# R450X.net
KiCad netlist of a schematic drawn in EAGLE
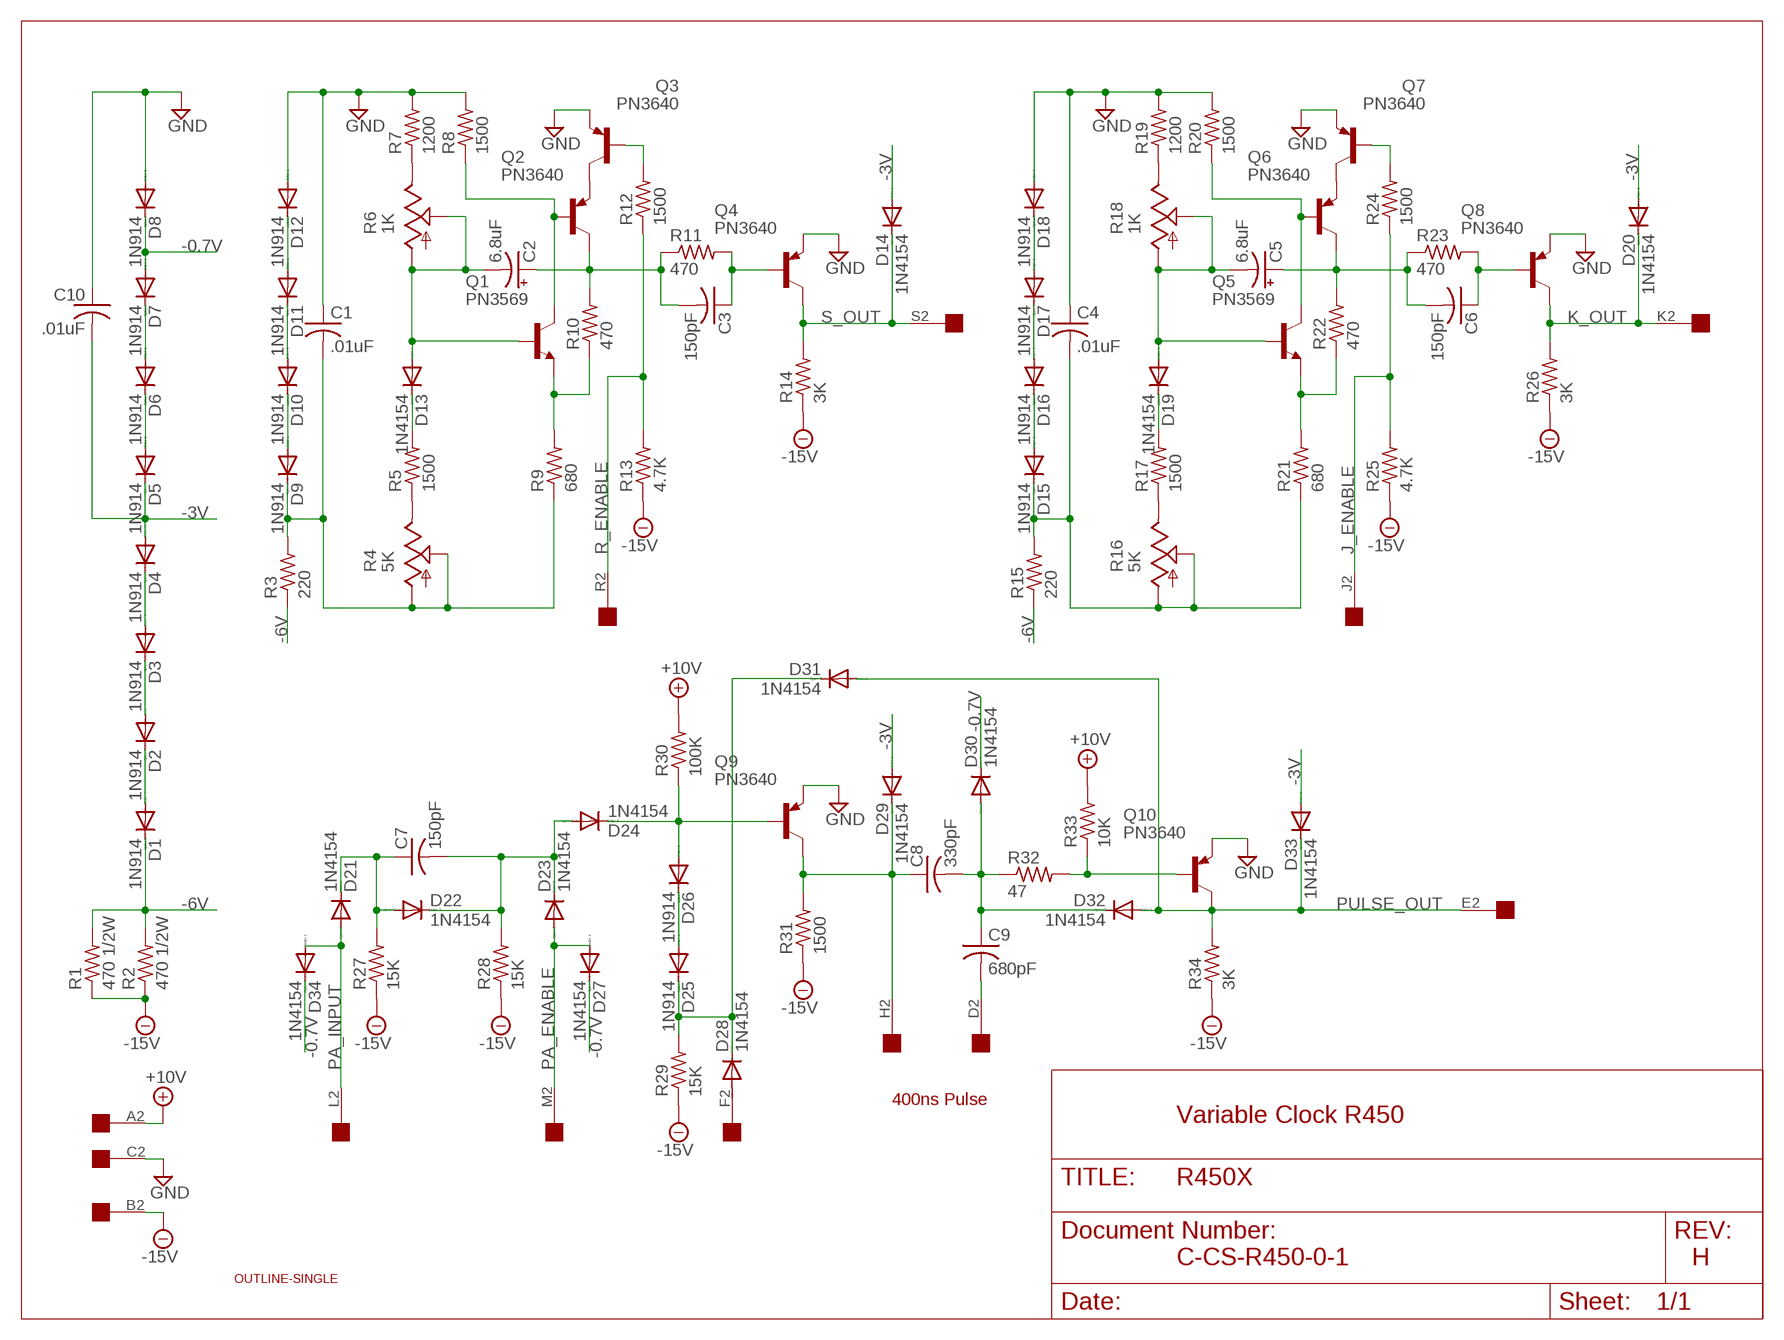
[diagram p0: schematic, sheet 1]

(export (version "E")
  (design (tool "Eeschema 10.0.6"))
  (components
    (comp (ref "C1")
      (value ".01uF")
      (footprint "eagle-import:C050-025X075")
      (libsource (lib "eagle-import") (part "C-US050-025X075"))
    )
    (comp (ref "C2")
      (value "6.8uF")
      (footprint "eagle-import:E12-4")
      (libsource (lib "eagle-import") (part "CPOL-USE12-4AXIAL"))
    )
    (comp (ref "C3")
      (value "150pF")
      (footprint "eagle-import:C075-032X103")
      (libsource (lib "eagle-import") (part "C-US075-032X103"))
    )
    (comp (ref "C4")
      (value ".01uF")
      (footprint "eagle-import:C050-025X075")
      (libsource (lib "eagle-import") (part "C-US050-025X075"))
    )
    (comp (ref "C5")
      (value "6.8uF")
      (footprint "eagle-import:E12-4")
      (libsource (lib "eagle-import") (part "CPOL-USE12-4AXIAL"))
    )
    (comp (ref "C6")
      (value "150pF")
      (footprint "eagle-import:C075-032X103")
      (libsource (lib "eagle-import") (part "C-US075-032X103"))
    )
    (comp (ref "C7")
      (value "150pF")
      (footprint "eagle-import:C075-032X103")
      (libsource (lib "eagle-import") (part "C-US075-032X103"))
    )
    (comp (ref "C8")
      (value "330pF")
      (footprint "eagle-import:C075-032X103")
      (libsource (lib "eagle-import") (part "C-US075-032X103"))
    )
    (comp (ref "C9")
      (value "680pF")
      (footprint "eagle-import:C075-032X103")
      (libsource (lib "eagle-import") (part "C-US075-032X103"))
    )
    (comp (ref "C10")
      (value ".01uF")
      (footprint "eagle-import:C050-025X075")
      (libsource (lib "eagle-import") (part "C-US050-025X075"))
    )
    (comp (ref "D1")
      (value "1N914")
      (footprint "eagle-import:DO35-10")
      (libsource (lib "eagle-import") (part "1N4148DO35-10"))
    )
    (comp (ref "D2")
      (value "1N914")
      (footprint "eagle-import:DO35-10")
      (libsource (lib "eagle-import") (part "1N4148DO35-10"))
    )
    (comp (ref "D3")
      (value "1N914")
      (footprint "eagle-import:DO35-10")
      (libsource (lib "eagle-import") (part "1N4148DO35-10"))
    )
    (comp (ref "D4")
      (value "1N914")
      (footprint "eagle-import:DO35-10")
      (libsource (lib "eagle-import") (part "1N4148DO35-10"))
    )
    (comp (ref "D5")
      (value "1N914")
      (footprint "eagle-import:DO35-10")
      (libsource (lib "eagle-import") (part "1N4148DO35-10"))
    )
    (comp (ref "D6")
      (value "1N914")
      (footprint "eagle-import:DO35-10")
      (libsource (lib "eagle-import") (part "1N4148DO35-10"))
    )
    (comp (ref "D7")
      (value "1N914")
      (footprint "eagle-import:DO35-10")
      (libsource (lib "eagle-import") (part "1N4148DO35-10"))
    )
    (comp (ref "D8")
      (value "1N914")
      (footprint "eagle-import:DO35-10")
      (libsource (lib "eagle-import") (part "1N4148DO35-10"))
    )
    (comp (ref "D9")
      (value "1N914")
      (footprint "eagle-import:DO35-10")
      (libsource (lib "eagle-import") (part "1N4148DO35-10"))
    )
    (comp (ref "D10")
      (value "1N914")
      (footprint "eagle-import:DO35-10")
      (libsource (lib "eagle-import") (part "1N4148DO35-10"))
    )
    (comp (ref "D11")
      (value "1N914")
      (footprint "eagle-import:DO35-10")
      (libsource (lib "eagle-import") (part "1N4148DO35-10"))
    )
    (comp (ref "D12")
      (value "1N914")
      (footprint "eagle-import:DO35-10")
      (libsource (lib "eagle-import") (part "1N4148DO35-10"))
    )
    (comp (ref "D13")
      (value "1N4154")
      (footprint "eagle-import:DO35-10")
      (libsource (lib "eagle-import") (part "1N4148DO35-10"))
    )
    (comp (ref "D14")
      (value "1N4154")
      (footprint "eagle-import:DO35-10")
      (libsource (lib "eagle-import") (part "1N4148DO35-10"))
    )
    (comp (ref "D15")
      (value "1N914")
      (footprint "eagle-import:DO35-10")
      (libsource (lib "eagle-import") (part "1N4148DO35-10"))
    )
    (comp (ref "D16")
      (value "1N914")
      (footprint "eagle-import:DO35-10")
      (libsource (lib "eagle-import") (part "1N4148DO35-10"))
    )
    (comp (ref "D17")
      (value "1N914")
      (footprint "eagle-import:DO35-10")
      (libsource (lib "eagle-import") (part "1N4148DO35-10"))
    )
    (comp (ref "D18")
      (value "1N914")
      (footprint "eagle-import:DO35-10")
      (libsource (lib "eagle-import") (part "1N4148DO35-10"))
    )
    (comp (ref "D19")
      (value "1N4154")
      (footprint "eagle-import:DO35-10")
      (libsource (lib "eagle-import") (part "1N4148DO35-10"))
    )
    (comp (ref "D20")
      (value "1N4154")
      (footprint "eagle-import:DO35-10")
      (libsource (lib "eagle-import") (part "1N4148DO35-10"))
    )
    (comp (ref "D21")
      (value "1N4154")
      (footprint "eagle-import:DO35-10")
      (libsource (lib "eagle-import") (part "1N4148DO35-10"))
    )
    (comp (ref "D22")
      (value "1N4154")
      (footprint "eagle-import:DO35-10")
      (libsource (lib "eagle-import") (part "1N4148DO35-10"))
    )
    (comp (ref "D23")
      (value "1N4154")
      (footprint "eagle-import:DO35-10")
      (libsource (lib "eagle-import") (part "1N4148DO35-10"))
    )
    (comp (ref "D24")
      (value "1N4154")
      (footprint "eagle-import:DO35-10")
      (libsource (lib "eagle-import") (part "1N4148DO35-10"))
    )
    (comp (ref "D25")
      (value "1N914")
      (footprint "eagle-import:DO35-10")
      (libsource (lib "eagle-import") (part "1N4148DO35-10"))
    )
    (comp (ref "D26")
      (value "1N914")
      (footprint "eagle-import:DO35-10")
      (libsource (lib "eagle-import") (part "1N4148DO35-10"))
    )
    (comp (ref "D27")
      (value "1N4154")
      (footprint "eagle-import:DO35-10")
      (libsource (lib "eagle-import") (part "1N4148DO35-10"))
    )
    (comp (ref "D28")
      (value "1N4154")
      (footprint "eagle-import:DO35-10")
      (libsource (lib "eagle-import") (part "1N4148DO35-10"))
    )
    (comp (ref "D29")
      (value "1N4154")
      (footprint "eagle-import:DO35-10")
      (libsource (lib "eagle-import") (part "1N4148DO35-10"))
    )
    (comp (ref "D30")
      (value "1N4154")
      (footprint "eagle-import:DO35-10")
      (libsource (lib "eagle-import") (part "1N4148DO35-10"))
    )
    (comp (ref "D31")
      (value "1N4154")
      (footprint "eagle-import:DO35-10")
      (libsource (lib "eagle-import") (part "1N4148DO35-10"))
    )
    (comp (ref "D32")
      (value "1N4154")
      (footprint "eagle-import:DO35-10")
      (libsource (lib "eagle-import") (part "1N4148DO35-10"))
    )
    (comp (ref "D33")
      (value "1N4154")
      (footprint "eagle-import:DO35-10")
      (libsource (lib "eagle-import") (part "1N4148DO35-10"))
    )
    (comp (ref "D34")
      (value "1N4154")
      (footprint "eagle-import:DO35-10")
      (libsource (lib "eagle-import") (part "1N4148DO35-10"))
    )
    (comp (ref "Q1")
      (value "PN3569")
      (footprint "eagle-import:TO5")
      (libsource (lib "eagle-import") (part "2N2102"))
    )
    (comp (ref "Q2")
      (value "PN3640")
      (footprint "eagle-import:TO39")
      (libsource (lib "eagle-import") (part "2N2904"))
    )
    (comp (ref "Q3")
      (value "PN3640")
      (footprint "eagle-import:TO39")
      (libsource (lib "eagle-import") (part "2N2904"))
    )
    (comp (ref "Q4")
      (value "PN3640")
      (footprint "eagle-import:TO39")
      (libsource (lib "eagle-import") (part "2N2904"))
    )
    (comp (ref "Q5")
      (value "PN3569")
      (footprint "eagle-import:TO5")
      (libsource (lib "eagle-import") (part "2N2102"))
    )
    (comp (ref "Q6")
      (value "PN3640")
      (footprint "eagle-import:TO39")
      (libsource (lib "eagle-import") (part "2N2904"))
    )
    (comp (ref "Q7")
      (value "PN3640")
      (footprint "eagle-import:TO39")
      (libsource (lib "eagle-import") (part "2N2904"))
    )
    (comp (ref "Q8")
      (value "PN3640")
      (footprint "eagle-import:TO39")
      (libsource (lib "eagle-import") (part "2N2904"))
    )
    (comp (ref "Q9")
      (value "PN3640")
      (footprint "eagle-import:TO39")
      (libsource (lib "eagle-import") (part "2N2904"))
    )
    (comp (ref "Q10")
      (value "PN3640")
      (footprint "eagle-import:TO39")
      (libsource (lib "eagle-import") (part "2N2904"))
    )
    (comp (ref "R1")
      (value "470 1/2W")
      (footprint "eagle-import:0411_15")
      (libsource (lib "eagle-import") (part "R-US_0411/15"))
    )
    (comp (ref "R2")
      (value "470 1/2W")
      (footprint "eagle-import:0411_15")
      (libsource (lib "eagle-import") (part "R-US_0411/15"))
    )
    (comp (ref "R3")
      (value "220")
      (footprint "eagle-import:0207_10")
      (libsource (lib "eagle-import") (part "R-US_0207/10"))
    )
    (comp (ref "R4")
      (value "5K")
      (footprint "eagle-import:CT6")
      (libsource (lib "eagle-import") (part "TRIM_US-CT6"))
    )
    (comp (ref "R5")
      (value "1500")
      (footprint "eagle-import:0207_10")
      (libsource (lib "eagle-import") (part "R-US_0207/10"))
    )
    (comp (ref "R6")
      (value "1K")
      (footprint "eagle-import:CT6")
      (libsource (lib "eagle-import") (part "TRIM_US-CT6"))
    )
    (comp (ref "R7")
      (value "1200")
      (footprint "eagle-import:0207_10")
      (libsource (lib "eagle-import") (part "R-US_0207/10"))
    )
    (comp (ref "R8")
      (value "1500")
      (footprint "eagle-import:0207_10")
      (libsource (lib "eagle-import") (part "R-US_0207/10"))
    )
    (comp (ref "R9")
      (value "680")
      (footprint "eagle-import:0207_10")
      (libsource (lib "eagle-import") (part "R-US_0207/10"))
    )
    (comp (ref "R10")
      (value "470")
      (footprint "eagle-import:0207_10")
      (libsource (lib "eagle-import") (part "R-US_0207/10"))
    )
    (comp (ref "R11")
      (value "470")
      (footprint "eagle-import:0207_10")
      (libsource (lib "eagle-import") (part "R-US_0207/10"))
    )
    (comp (ref "R12")
      (value "1500")
      (footprint "eagle-import:0207_10")
      (libsource (lib "eagle-import") (part "R-US_0207/10"))
    )
    (comp (ref "R13")
      (value "4.7K")
      (footprint "eagle-import:0207_10")
      (libsource (lib "eagle-import") (part "R-US_0207/10"))
    )
    (comp (ref "R14")
      (value "3K")
      (footprint "eagle-import:0207_10")
      (libsource (lib "eagle-import") (part "R-US_0207/10"))
    )
    (comp (ref "R15")
      (value "220")
      (footprint "eagle-import:0207_10")
      (libsource (lib "eagle-import") (part "R-US_0207/10"))
    )
    (comp (ref "R16")
      (value "5K")
      (footprint "eagle-import:CT6")
      (libsource (lib "eagle-import") (part "TRIM_US-CT6"))
    )
    (comp (ref "R17")
      (value "1500")
      (footprint "eagle-import:0207_10")
      (libsource (lib "eagle-import") (part "R-US_0207/10"))
    )
    (comp (ref "R18")
      (value "1K")
      (footprint "eagle-import:CT6")
      (libsource (lib "eagle-import") (part "TRIM_US-CT6"))
    )
    (comp (ref "R19")
      (value "1200")
      (footprint "eagle-import:0207_10")
      (libsource (lib "eagle-import") (part "R-US_0207/10"))
    )
    (comp (ref "R20")
      (value "1500")
      (footprint "eagle-import:0207_10")
      (libsource (lib "eagle-import") (part "R-US_0207/10"))
    )
    (comp (ref "R21")
      (value "680")
      (footprint "eagle-import:0207_10")
      (libsource (lib "eagle-import") (part "R-US_0207/10"))
    )
    (comp (ref "R22")
      (value "470")
      (footprint "eagle-import:0207_10")
      (libsource (lib "eagle-import") (part "R-US_0207/10"))
    )
    (comp (ref "R23")
      (value "470")
      (footprint "eagle-import:0207_10")
      (libsource (lib "eagle-import") (part "R-US_0207/10"))
    )
    (comp (ref "R24")
      (value "1500")
      (footprint "eagle-import:0207_10")
      (libsource (lib "eagle-import") (part "R-US_0207/10"))
    )
    (comp (ref "R25")
      (value "4.7K")
      (footprint "eagle-import:0207_10")
      (libsource (lib "eagle-import") (part "R-US_0207/10"))
    )
    (comp (ref "R26")
      (value "3K")
      (footprint "eagle-import:0207_10")
      (libsource (lib "eagle-import") (part "R-US_0207/10"))
    )
    (comp (ref "R27")
      (value "15K")
      (footprint "eagle-import:0207_10")
      (libsource (lib "eagle-import") (part "R-US_0207/10"))
    )
    (comp (ref "R28")
      (value "15K")
      (footprint "eagle-import:0207_10")
      (libsource (lib "eagle-import") (part "R-US_0207/10"))
    )
    (comp (ref "R29")
      (value "15K")
      (footprint "eagle-import:0207_10")
      (libsource (lib "eagle-import") (part "R-US_0207/10"))
    )
    (comp (ref "R30")
      (value "100K")
      (footprint "eagle-import:0207_10")
      (libsource (lib "eagle-import") (part "R-US_0207/10"))
    )
    (comp (ref "R31")
      (value "1500")
      (footprint "eagle-import:0207_10")
      (libsource (lib "eagle-import") (part "R-US_0207/10"))
    )
    (comp (ref "R32")
      (value "47")
      (footprint "eagle-import:0207_10")
      (libsource (lib "eagle-import") (part "R-US_0207/10"))
    )
    (comp (ref "R33")
      (value "10K")
      (footprint "eagle-import:0207_10")
      (libsource (lib "eagle-import") (part "R-US_0207/10"))
    )
    (comp (ref "R34")
      (value "3K")
      (footprint "eagle-import:0207_10")
      (libsource (lib "eagle-import") (part "R-US_0207/10"))
    )
    (comp (ref "U$1")
      (value "OUTLINE-SINGLE")
      (footprint "eagle-import:SINGLE")
      (libsource (lib "eagle-import") (part "OUTLINE-SINGLE"))
    )
    (comp (ref "U$2")
      (value "EDGE-1")
      (footprint "eagle-import:EDGE-CON1")
      (libsource (lib "eagle-import") (part "EDGE-1"))
    )
  )
  (nets
    (net (code "1") (name "+10V") (class "Default")
      (node (ref "R30") (pin "2") (pinfunction "2_2") (pintype "passive"))
      (node (ref "R33") (pin "2") (pinfunction "2_2") (pintype "passive"))
      (node (ref "U$2") (pin "A2") (pinfunction "1_A2") (pintype "bidirectional"))
    )
    (net (code "2") (name "-15V") (class "Default")
      (node (ref "R1") (pin "1") (pinfunction "1_1") (pintype "passive"))
      (node (ref "R13") (pin "1") (pinfunction "1_1") (pintype "passive"))
      (node (ref "R14") (pin "1") (pinfunction "1_1") (pintype "passive"))
      (node (ref "R2") (pin "1") (pinfunction "1_1") (pintype "passive"))
      (node (ref "R25") (pin "1") (pinfunction "1_1") (pintype "passive"))
      (node (ref "R26") (pin "1") (pinfunction "1_1") (pintype "passive"))
      (node (ref "R27") (pin "1") (pinfunction "1_1") (pintype "passive"))
      (node (ref "R28") (pin "1") (pinfunction "1_1") (pintype "passive"))
      (node (ref "R29") (pin "1") (pinfunction "1_1") (pintype "passive"))
      (node (ref "R31") (pin "1") (pinfunction "1_1") (pintype "passive"))
      (node (ref "R34") (pin "1") (pinfunction "1_1") (pintype "passive"))
      (node (ref "U$2") (pin "B2") (pinfunction "1_B2") (pintype "bidirectional"))
    )
    (net (code "3") (name "/-0.7V") (class "Default")
      (node (ref "D27") (pin "C") (pinfunction "C_C") (pintype "passive"))
      (node (ref "D30") (pin "C") (pinfunction "C_C") (pintype "passive"))
      (node (ref "D34") (pin "C") (pinfunction "C_C") (pintype "passive"))
      (node (ref "D7") (pin "A") (pinfunction "A_A") (pintype "passive"))
      (node (ref "D8") (pin "C") (pinfunction "C_C") (pintype "passive"))
    )
    (net (code "4") (name "/-3V") (class "Default")
      (node (ref "C10") (pin "2") (pinfunction "2_2") (pintype "passive"))
      (node (ref "D14") (pin "A") (pinfunction "A_A") (pintype "passive"))
      (node (ref "D20") (pin "A") (pinfunction "A_A") (pintype "passive"))
      (node (ref "D29") (pin "A") (pinfunction "A_A") (pintype "passive"))
      (node (ref "D33") (pin "A") (pinfunction "A_A") (pintype "passive"))
      (node (ref "D4") (pin "A") (pinfunction "A_A") (pintype "passive"))
      (node (ref "D5") (pin "C") (pinfunction "C_C") (pintype "passive"))
    )
    (net (code "5") (name "/-6V") (class "Default")
      (node (ref "D1") (pin "C") (pinfunction "C_C") (pintype "passive"))
      (node (ref "R1") (pin "2") (pinfunction "2_2") (pintype "passive"))
      (node (ref "R15") (pin "1") (pinfunction "1_1") (pintype "passive"))
      (node (ref "R2") (pin "2") (pinfunction "2_2") (pintype "passive"))
      (node (ref "R3") (pin "1") (pinfunction "1_1") (pintype "passive"))
    )
    (net (code "6") (name "/J_ENABLE") (class "Default")
      (node (ref "R24") (pin "1") (pinfunction "1_1") (pintype "passive"))
      (node (ref "R25") (pin "2") (pinfunction "2_2") (pintype "passive"))
      (node (ref "U$2") (pin "J2") (pinfunction "1_J2") (pintype "bidirectional"))
    )
    (net (code "7") (name "/K_OUT") (class "Default")
      (node (ref "D20") (pin "C") (pinfunction "C_C") (pintype "passive"))
      (node (ref "Q8") (pin "3") (pinfunction "C_3") (pintype "passive"))
      (node (ref "R26") (pin "2") (pinfunction "2_2") (pintype "passive"))
      (node (ref "U$2") (pin "K2") (pinfunction "1_K2") (pintype "bidirectional"))
    )
    (net (code "8") (name "/PA_ENABLE") (class "Default")
      (node (ref "D23") (pin "A") (pinfunction "A_A") (pintype "passive"))
      (node (ref "D27") (pin "A") (pinfunction "A_A") (pintype "passive"))
      (node (ref "U$2") (pin "M2") (pinfunction "1_M2") (pintype "bidirectional"))
    )
    (net (code "9") (name "/PA_INPUT") (class "Default")
      (node (ref "D21") (pin "A") (pinfunction "A_A") (pintype "passive"))
      (node (ref "D34") (pin "A") (pinfunction "A_A") (pintype "passive"))
      (node (ref "U$2") (pin "L2") (pinfunction "1_L2") (pintype "bidirectional"))
    )
    (net (code "10") (name "/PULSE_OUT") (class "Default")
      (node (ref "D31") (pin "A") (pinfunction "A_A") (pintype "passive"))
      (node (ref "D32") (pin "A") (pinfunction "A_A") (pintype "passive"))
      (node (ref "D33") (pin "C") (pinfunction "C_C") (pintype "passive"))
      (node (ref "Q10") (pin "3") (pinfunction "C_3") (pintype "passive"))
      (node (ref "R34") (pin "2") (pinfunction "2_2") (pintype "passive"))
      (node (ref "U$2") (pin "E2") (pinfunction "1_E2") (pintype "bidirectional"))
    )
    (net (code "11") (name "/R_ENABLE") (class "Default")
      (node (ref "R12") (pin "1") (pinfunction "1_1") (pintype "passive"))
      (node (ref "R13") (pin "2") (pinfunction "2_2") (pintype "passive"))
      (node (ref "U$2") (pin "R2") (pinfunction "1_R2") (pintype "bidirectional"))
    )
    (net (code "12") (name "/S_OUT") (class "Default")
      (node (ref "D14") (pin "C") (pinfunction "C_C") (pintype "passive"))
      (node (ref "Q4") (pin "3") (pinfunction "C_3") (pintype "passive"))
      (node (ref "R14") (pin "2") (pinfunction "2_2") (pintype "passive"))
      (node (ref "U$2") (pin "S2") (pinfunction "1_S2") (pintype "bidirectional"))
    )
    (net (code "13") (name "GND") (class "Default")
      (node (ref "C1") (pin "1") (pinfunction "1_1") (pintype "passive"))
      (node (ref "C10") (pin "1") (pinfunction "1_1") (pintype "passive"))
      (node (ref "C4") (pin "1") (pinfunction "1_1") (pintype "passive"))
      (node (ref "D12") (pin "A") (pinfunction "A_A") (pintype "passive"))
      (node (ref "D18") (pin "A") (pinfunction "A_A") (pintype "passive"))
      (node (ref "D8") (pin "A") (pinfunction "A_A") (pintype "passive"))
      (node (ref "Q10") (pin "1") (pinfunction "E_1") (pintype "passive"))
      (node (ref "Q3") (pin "1") (pinfunction "E_1") (pintype "passive"))
      (node (ref "Q4") (pin "1") (pinfunction "E_1") (pintype "passive"))
      (node (ref "Q7") (pin "1") (pinfunction "E_1") (pintype "passive"))
      (node (ref "Q8") (pin "1") (pinfunction "E_1") (pintype "passive"))
      (node (ref "Q9") (pin "1") (pinfunction "E_1") (pintype "passive"))
      (node (ref "R19") (pin "2") (pinfunction "2_2") (pintype "passive"))
      (node (ref "R20") (pin "2") (pinfunction "2_2") (pintype "passive"))
      (node (ref "R7") (pin "2") (pinfunction "2_2") (pintype "passive"))
      (node (ref "R8") (pin "2") (pinfunction "2_2") (pintype "passive"))
      (node (ref "U$2") (pin "C2") (pinfunction "1_C2") (pintype "bidirectional"))
    )
    (net (code "14") (name "Net-(C1-Pad2)") (class "Default")
      (node (ref "C1") (pin "2") (pinfunction "2_2") (pintype "passive"))
      (node (ref "D9") (pin "C") (pinfunction "C_C") (pintype "passive"))
      (node (ref "R3") (pin "2") (pinfunction "2_2") (pintype "passive"))
      (node (ref "R4") (pin "A") (pinfunction "A_A") (pintype "passive"))
      (node (ref "R4") (pin "S") (pinfunction "S_S") (pintype "passive"))
      (node (ref "R9") (pin "1") (pinfunction "1_1") (pintype "passive"))
    )
    (net (code "15") (name "Net-(C4-Pad2)") (class "Default")
      (node (ref "C4") (pin "2") (pinfunction "2_2") (pintype "passive"))
      (node (ref "D15") (pin "C") (pinfunction "C_C") (pintype "passive"))
      (node (ref "R15") (pin "2") (pinfunction "2_2") (pintype "passive"))
      (node (ref "R16") (pin "A") (pinfunction "A_A") (pintype "passive"))
      (node (ref "R16") (pin "S") (pinfunction "S_S") (pintype "passive"))
      (node (ref "R21") (pin "1") (pinfunction "1_1") (pintype "passive"))
    )
    (net (code "16") (name "Net-(C7-Pad1)") (class "Default")
      (node (ref "C7") (pin "1") (pinfunction "1_1") (pintype "passive"))
      (node (ref "D21") (pin "C") (pinfunction "C_C") (pintype "passive"))
      (node (ref "D22") (pin "A") (pinfunction "A_A") (pintype "passive"))
      (node (ref "R27") (pin "2") (pinfunction "2_2") (pintype "passive"))
    )
    (net (code "17") (name "Net-(C7-Pad2)") (class "Default")
      (node (ref "C7") (pin "2") (pinfunction "2_2") (pintype "passive"))
      (node (ref "D22") (pin "C") (pinfunction "C_C") (pintype "passive"))
      (node (ref "D23") (pin "C") (pinfunction "C_C") (pintype "passive"))
      (node (ref "D24") (pin "A") (pinfunction "A_A") (pintype "passive"))
      (node (ref "R28") (pin "2") (pinfunction "2_2") (pintype "passive"))
    )
    (net (code "18") (name "Net-(C8-Pad2)") (class "Default")
      (node (ref "C8") (pin "2") (pinfunction "2_2") (pintype "passive"))
      (node (ref "C9") (pin "1") (pinfunction "1_1") (pintype "passive"))
      (node (ref "D30") (pin "A") (pinfunction "A_A") (pintype "passive"))
      (node (ref "D32") (pin "C") (pinfunction "C_C") (pintype "passive"))
      (node (ref "R32") (pin "1") (pinfunction "1_1") (pintype "passive"))
    )
    (net (code "19") (name "Net-(D1-PadA)") (class "Default")
      (node (ref "D1") (pin "A") (pinfunction "A_A") (pintype "passive"))
      (node (ref "D2") (pin "C") (pinfunction "C_C") (pintype "passive"))
    )
    (net (code "20") (name "Net-(D2-PadA)") (class "Default")
      (node (ref "D2") (pin "A") (pinfunction "A_A") (pintype "passive"))
      (node (ref "D3") (pin "C") (pinfunction "C_C") (pintype "passive"))
    )
    (net (code "21") (name "Net-(D3-PadA)") (class "Default")
      (node (ref "D3") (pin "A") (pinfunction "A_A") (pintype "passive"))
      (node (ref "D4") (pin "C") (pinfunction "C_C") (pintype "passive"))
    )
    (net (code "22") (name "Net-(D5-PadA)") (class "Default")
      (node (ref "D5") (pin "A") (pinfunction "A_A") (pintype "passive"))
      (node (ref "D6") (pin "C") (pinfunction "C_C") (pintype "passive"))
    )
    (net (code "23") (name "Net-(D6-PadA)") (class "Default")
      (node (ref "D6") (pin "A") (pinfunction "A_A") (pintype "passive"))
      (node (ref "D7") (pin "C") (pinfunction "C_C") (pintype "passive"))
    )
    (net (code "24") (name "Net-(D10-PadA)") (class "Default")
      (node (ref "D10") (pin "A") (pinfunction "A_A") (pintype "passive"))
      (node (ref "D11") (pin "C") (pinfunction "C_C") (pintype "passive"))
    )
    (net (code "25") (name "Net-(D10-PadC)") (class "Default")
      (node (ref "D10") (pin "C") (pinfunction "C_C") (pintype "passive"))
      (node (ref "D9") (pin "A") (pinfunction "A_A") (pintype "passive"))
    )
    (net (code "26") (name "Net-(D11-PadA)") (class "Default")
      (node (ref "D11") (pin "A") (pinfunction "A_A") (pintype "passive"))
      (node (ref "D12") (pin "C") (pinfunction "C_C") (pintype "passive"))
    )
    (net (code "27") (name "Net-(D13-PadC)") (class "Default")
      (node (ref "D13") (pin "C") (pinfunction "C_C") (pintype "passive"))
      (node (ref "R5") (pin "2") (pinfunction "2_2") (pintype "passive"))
    )
    (net (code "28") (name "Net-(D15-PadA)") (class "Default")
      (node (ref "D15") (pin "A") (pinfunction "A_A") (pintype "passive"))
      (node (ref "D16") (pin "C") (pinfunction "C_C") (pintype "passive"))
    )
    (net (code "29") (name "Net-(D16-PadA)") (class "Default")
      (node (ref "D16") (pin "A") (pinfunction "A_A") (pintype "passive"))
      (node (ref "D17") (pin "C") (pinfunction "C_C") (pintype "passive"))
    )
    (net (code "30") (name "Net-(D17-PadA)") (class "Default")
      (node (ref "D17") (pin "A") (pinfunction "A_A") (pintype "passive"))
      (node (ref "D18") (pin "C") (pinfunction "C_C") (pintype "passive"))
    )
    (net (code "31") (name "Net-(D19-PadC)") (class "Default")
      (node (ref "D19") (pin "C") (pinfunction "C_C") (pintype "passive"))
      (node (ref "R17") (pin "2") (pinfunction "2_2") (pintype "passive"))
    )
    (net (code "32") (name "Net-(D25-PadA)") (class "Default")
      (node (ref "D25") (pin "A") (pinfunction "A_A") (pintype "passive"))
      (node (ref "D26") (pin "C") (pinfunction "C_C") (pintype "passive"))
    )
    (net (code "33") (name "Net-(D25-PadC)") (class "Default")
      (node (ref "D25") (pin "C") (pinfunction "C_C") (pintype "passive"))
      (node (ref "D28") (pin "C") (pinfunction "C_C") (pintype "passive"))
      (node (ref "D31") (pin "C") (pinfunction "C_C") (pintype "passive"))
      (node (ref "R29") (pin "2") (pinfunction "2_2") (pintype "passive"))
    )
    (net (code "34") (name "Net-(Q1-B)") (class "Default")
      (node (ref "C2") (pin "-") (pinfunction "-_-") (pintype "passive"))
      (node (ref "D13") (pin "A") (pinfunction "A_A") (pintype "passive"))
      (node (ref "Q1") (pin "2") (pinfunction "B_2") (pintype "passive"))
      (node (ref "R6") (pin "A") (pinfunction "A_A") (pintype "passive"))
      (node (ref "R6") (pin "S") (pinfunction "S_S") (pintype "passive"))
    )
    (net (code "35") (name "Net-(Q1-C)") (class "Default")
      (node (ref "Q1") (pin "3") (pinfunction "C_3") (pintype "passive"))
      (node (ref "Q2") (pin "2") (pinfunction "B_2") (pintype "passive"))
      (node (ref "R8") (pin "1") (pinfunction "1_1") (pintype "passive"))
    )
    (net (code "36") (name "Net-(Q1-E)") (class "Default")
      (node (ref "Q1") (pin "1") (pinfunction "E_1") (pintype "passive"))
      (node (ref "R10") (pin "1") (pinfunction "1_1") (pintype "passive"))
      (node (ref "R9") (pin "2") (pinfunction "2_2") (pintype "passive"))
    )
    (net (code "37") (name "Net-(Q2-C)") (class "Default")
      (node (ref "C2") (pin "+") (pinfunction "+_+") (pintype "passive"))
      (node (ref "C3") (pin "2") (pinfunction "2_2") (pintype "passive"))
      (node (ref "Q2") (pin "3") (pinfunction "C_3") (pintype "passive"))
      (node (ref "R10") (pin "2") (pinfunction "2_2") (pintype "passive"))
      (node (ref "R11") (pin "1") (pinfunction "1_1") (pintype "passive"))
    )
    (net (code "38") (name "Net-(Q2-E)") (class "Default")
      (node (ref "Q2") (pin "1") (pinfunction "E_1") (pintype "passive"))
      (node (ref "Q3") (pin "3") (pinfunction "C_3") (pintype "passive"))
    )
    (net (code "39") (name "Net-(Q3-B)") (class "Default")
      (node (ref "Q3") (pin "2") (pinfunction "B_2") (pintype "passive"))
      (node (ref "R12") (pin "2") (pinfunction "2_2") (pintype "passive"))
    )
    (net (code "40") (name "Net-(Q4-B)") (class "Default")
      (node (ref "C3") (pin "1") (pinfunction "1_1") (pintype "passive"))
      (node (ref "Q4") (pin "2") (pinfunction "B_2") (pintype "passive"))
      (node (ref "R11") (pin "2") (pinfunction "2_2") (pintype "passive"))
    )
    (net (code "41") (name "Net-(Q5-B)") (class "Default")
      (node (ref "C5") (pin "-") (pinfunction "-_-") (pintype "passive"))
      (node (ref "D19") (pin "A") (pinfunction "A_A") (pintype "passive"))
      (node (ref "Q5") (pin "2") (pinfunction "B_2") (pintype "passive"))
      (node (ref "R18") (pin "A") (pinfunction "A_A") (pintype "passive"))
      (node (ref "R18") (pin "S") (pinfunction "S_S") (pintype "passive"))
    )
    (net (code "42") (name "Net-(Q5-C)") (class "Default")
      (node (ref "Q5") (pin "3") (pinfunction "C_3") (pintype "passive"))
      (node (ref "Q6") (pin "2") (pinfunction "B_2") (pintype "passive"))
      (node (ref "R20") (pin "1") (pinfunction "1_1") (pintype "passive"))
    )
    (net (code "43") (name "Net-(Q5-E)") (class "Default")
      (node (ref "Q5") (pin "1") (pinfunction "E_1") (pintype "passive"))
      (node (ref "R21") (pin "2") (pinfunction "2_2") (pintype "passive"))
      (node (ref "R22") (pin "1") (pinfunction "1_1") (pintype "passive"))
    )
    (net (code "44") (name "Net-(Q6-C)") (class "Default")
      (node (ref "C5") (pin "+") (pinfunction "+_+") (pintype "passive"))
      (node (ref "C6") (pin "2") (pinfunction "2_2") (pintype "passive"))
      (node (ref "Q6") (pin "3") (pinfunction "C_3") (pintype "passive"))
      (node (ref "R22") (pin "2") (pinfunction "2_2") (pintype "passive"))
      (node (ref "R23") (pin "1") (pinfunction "1_1") (pintype "passive"))
    )
    (net (code "45") (name "Net-(Q6-E)") (class "Default")
      (node (ref "Q6") (pin "1") (pinfunction "E_1") (pintype "passive"))
      (node (ref "Q7") (pin "3") (pinfunction "C_3") (pintype "passive"))
    )
    (net (code "46") (name "Net-(Q7-B)") (class "Default")
      (node (ref "Q7") (pin "2") (pinfunction "B_2") (pintype "passive"))
      (node (ref "R24") (pin "2") (pinfunction "2_2") (pintype "passive"))
    )
    (net (code "47") (name "Net-(Q8-B)") (class "Default")
      (node (ref "C6") (pin "1") (pinfunction "1_1") (pintype "passive"))
      (node (ref "Q8") (pin "2") (pinfunction "B_2") (pintype "passive"))
      (node (ref "R23") (pin "2") (pinfunction "2_2") (pintype "passive"))
    )
    (net (code "48") (name "Net-(Q9-B)") (class "Default")
      (node (ref "D24") (pin "C") (pinfunction "C_C") (pintype "passive"))
      (node (ref "D26") (pin "A") (pinfunction "A_A") (pintype "passive"))
      (node (ref "Q9") (pin "2") (pinfunction "B_2") (pintype "passive"))
      (node (ref "R30") (pin "1") (pinfunction "1_1") (pintype "passive"))
    )
    (net (code "49") (name "Net-(Q9-C)") (class "Default")
      (node (ref "C8") (pin "1") (pinfunction "1_1") (pintype "passive"))
      (node (ref "D29") (pin "C") (pinfunction "C_C") (pintype "passive"))
      (node (ref "Q9") (pin "3") (pinfunction "C_3") (pintype "passive"))
      (node (ref "R31") (pin "2") (pinfunction "2_2") (pintype "passive"))
      (node (ref "U$2") (pin "H2") (pinfunction "1_H2") (pintype "bidirectional"))
    )
    (net (code "50") (name "Net-(Q10-B)") (class "Default")
      (node (ref "Q10") (pin "2") (pinfunction "B_2") (pintype "passive"))
      (node (ref "R32") (pin "2") (pinfunction "2_2") (pintype "passive"))
      (node (ref "R33") (pin "1") (pinfunction "1_1") (pintype "passive"))
    )
    (net (code "51") (name "Net-(R4-PadE)") (class "Default")
      (node (ref "R4") (pin "E") (pinfunction "E_E") (pintype "passive"))
      (node (ref "R5") (pin "1") (pinfunction "1_1") (pintype "passive"))
    )
    (net (code "52") (name "Net-(R6-PadE)") (class "Default")
      (node (ref "R6") (pin "E") (pinfunction "E_E") (pintype "passive"))
      (node (ref "R7") (pin "1") (pinfunction "1_1") (pintype "passive"))
    )
    (net (code "53") (name "Net-(R16-PadE)") (class "Default")
      (node (ref "R16") (pin "E") (pinfunction "E_E") (pintype "passive"))
      (node (ref "R17") (pin "1") (pinfunction "1_1") (pintype "passive"))
    )
    (net (code "54") (name "Net-(R18-PadE)") (class "Default")
      (node (ref "R18") (pin "E") (pinfunction "E_E") (pintype "passive"))
      (node (ref "R19") (pin "1") (pinfunction "1_1") (pintype "passive"))
    )
    (net (code "55") (name "Net-(U$2D-1)") (class "Default")
      (node (ref "C9") (pin "2") (pinfunction "2_2") (pintype "passive"))
      (node (ref "U$2") (pin "D2") (pinfunction "1_D2") (pintype "bidirectional"))
    )
    (net (code "56") (name "Net-(U$2F-1)") (class "Default")
      (node (ref "D28") (pin "A") (pinfunction "A_A") (pintype "passive"))
      (node (ref "U$2") (pin "F2") (pinfunction "1_F2") (pintype "bidirectional"))
    )
  )
)
